# 2022_AESK_UAV_EXT_CONN.net
KiCad netlist of a schematic drawn in Altium Designer
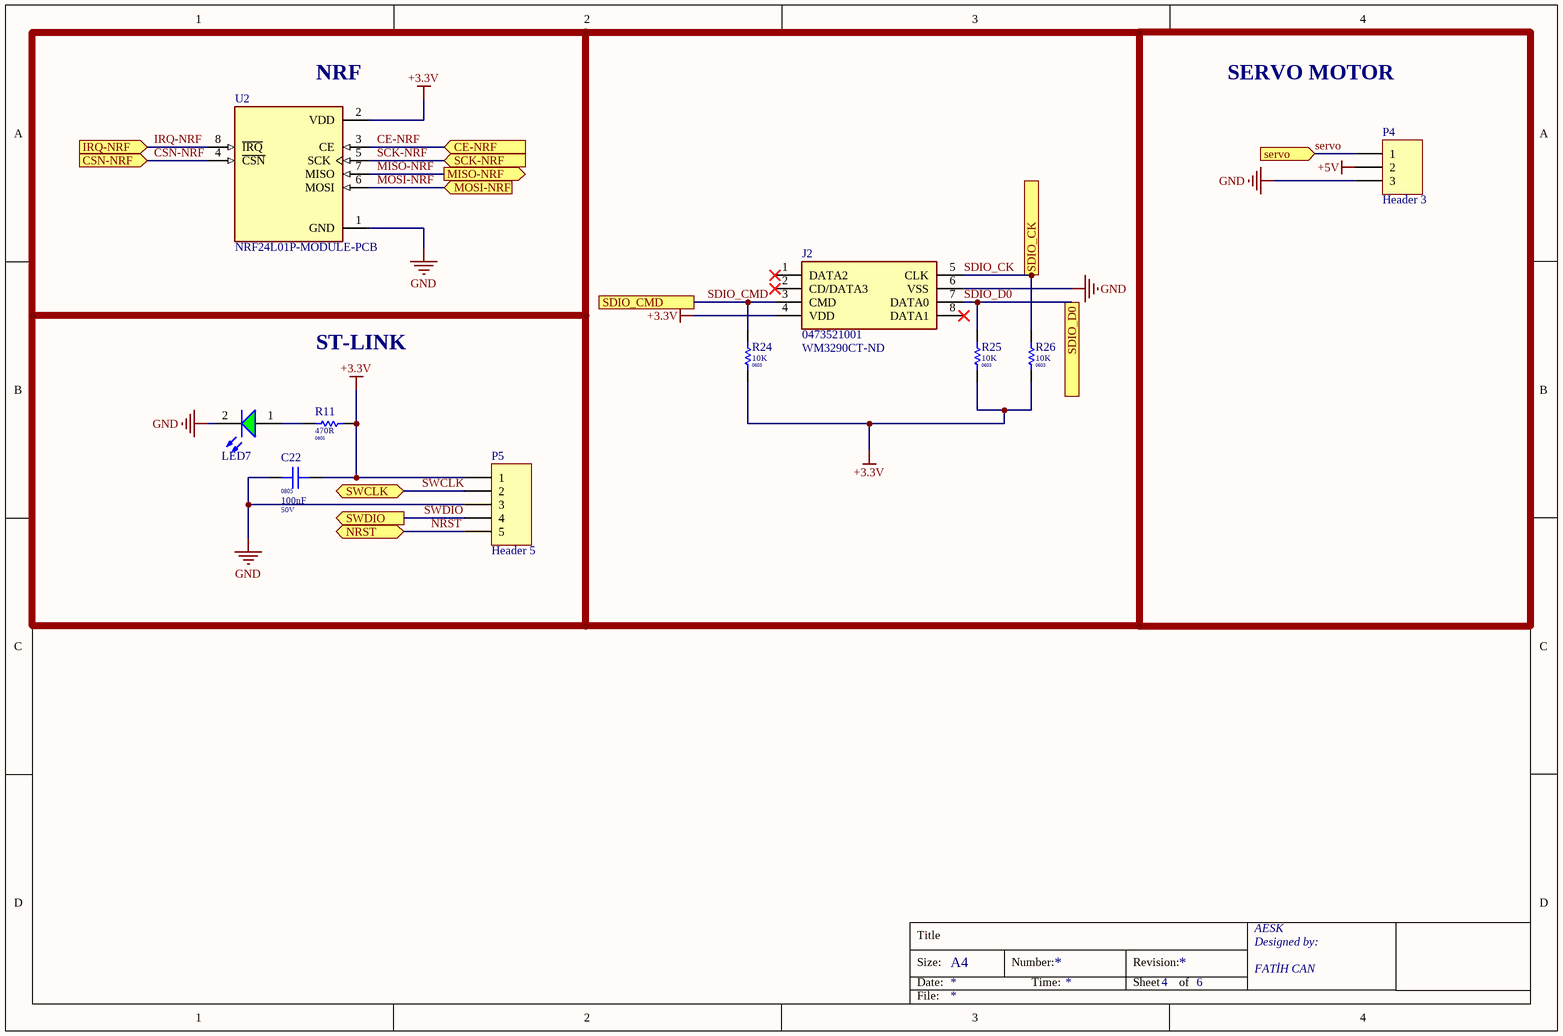
[diagram p0: 2022_AESK_UAV_EXT_CONN.SchDoc]

(export (version "E")
  (design (tool "Eeschema 10.0.6"))
  (components
    (comp (ref "C22")
      (value "100nF")
      (footprint "CAPC 0805")
      (description "Capacitor Ceramic 100nF 50V 0805")
      (fields
        (field (name "TOLERANCE") "%10")
        (field (name "PACKAGE / CASE") "0805")
        (field (name "VOLTAGE") "50V")
        (field (name "PART NUMBER") "CAPC0572")
      )
      (libsource (lib "AESK Database Library") (part "NPCapacitor"))
    )
    (comp (ref "J2")
      (value "0473521001")
      (footprint "47352-1001")
      (description "microSD Card Module")
      (fields (field (name "SUPPLIER PART NUMBER 1") "WM3290CT-ND"))
      (libsource (lib "2022_AESK_UAV") (part "0473521001"))
    )
    (comp (ref "LED7")
      (value "~")
      (footprint "LED GREEN 0805")
      (description "LED")
      (libsource (lib "Diodes_GESK") (part "LED GREEN"))
    )
    (comp (ref "P4")
      (value "Header 3")
      (footprint "HDR1X3")
      (description "Header, 3-Pin")
      (fields (field (name "PUBLISHER") "Altium Limited"))
      (libsource (lib "Miscellaneous Connectors") (part "Header 3"))
    )
    (comp (ref "P5")
      (value "Header 5")
      (footprint "HDR1X5")
      (description "Header, 5-Pin")
      (fields (field (name "PUBLISHER") "Altium Limited"))
      (libsource (lib "Miscellaneous Connectors") (part "Header 5"))
    )
    (comp (ref "R11")
      (value "470R")
      (footprint "RESC 0805")
      (description "470R 0805")
      (fields
        (field (name "TOLERANCE") "%5")
        (field (name "POWER") "1/10W")
        (field (name "PACKAGE / CASE") "0805")
      )
      (libsource (lib "AESK Database Library") (part "Resistor"))
    )
    (comp (ref "R24")
      (value "10K")
      (footprint "RESC 0603")
      (description "10K 0603")
      (fields
        (field (name "TOLERANCE") "%5")
        (field (name "POWER") "1/10W")
        (field (name "PACKAGE / CASE") "0603")
      )
      (libsource (lib "AESK Database Library") (part "Resistor"))
    )
    (comp (ref "R25")
      (value "10K")
      (footprint "RESC 0603")
      (description "10K 0603")
      (fields
        (field (name "TOLERANCE") "%5")
        (field (name "POWER") "1/10W")
        (field (name "PACKAGE / CASE") "0603")
      )
      (libsource (lib "AESK Database Library") (part "Resistor"))
    )
    (comp (ref "R26")
      (value "10K")
      (footprint "RESC 0603")
      (description "10K 0603")
      (fields
        (field (name "TOLERANCE") "%5")
        (field (name "POWER") "1/10W")
        (field (name "PACKAGE / CASE") "0603")
      )
      (libsource (lib "AESK Database Library") (part "Resistor"))
    )
    (comp (ref "U2")
      (value "NRF24L01P-MODULE-PCB")
      (footprint "nrf")
      (description "- Transceiver For Use With nRF24L01+")
      (fields (field (name "MF") "Nordic Semiconductor"))
      (libsource (lib "UAV_UcusKontrolKartı_Sematik_Kutuphane") (part "NRF24L01P-MODULE-PCB"))
    )
  )
  (nets
    (net (code "1") (name "+3.3V") (class "Default")
      (node (ref "C22") (pin "2") (pinfunction "2_2") (pintype "passive"))
      (node (ref "J2") (pin "4") (pinfunction "VDD_4") (pintype "passive"))
      (node (ref "P5") (pin "1") (pinfunction "1_1") (pintype "passive"))
      (node (ref "R11") (pin "2") (pinfunction "2_2") (pintype "passive"))
      (node (ref "R24") (pin "1") (pinfunction "1_1") (pintype "passive"))
      (node (ref "R25") (pin "1") (pinfunction "1_1") (pintype "passive"))
      (node (ref "R26") (pin "1") (pinfunction "1_1") (pintype "passive"))
      (node (ref "U2") (pin "2") (pinfunction "VDD_2") (pintype "power_in"))
    )
    (net (code "2") (name "+5V") (class "Default")
      (node (ref "P4") (pin "2") (pinfunction "2_2") (pintype "passive"))
    )
    (net (code "3") (name "/CE-NRF") (class "Default")
      (node (ref "U2") (pin "3") (pinfunction "CE_3") (pintype "input"))
    )
    (net (code "4") (name "/CSN-NRF") (class "Default")
      (node (ref "U2") (pin "4") (pinfunction "~{CSN}_4") (pintype "input"))
    )
    (net (code "5") (name "/IRQ-NRF") (class "Default")
      (node (ref "U2") (pin "8") (pinfunction "~{IRQ}_8") (pintype "input"))
    )
    (net (code "6") (name "/MISO-NRF") (class "Default")
      (node (ref "U2") (pin "7") (pinfunction "MISO_7") (pintype "input"))
    )
    (net (code "7") (name "/MOSI-NRF") (class "Default")
      (node (ref "U2") (pin "6") (pinfunction "MOSI_6") (pintype "input"))
    )
    (net (code "8") (name "/NRST") (class "Default")
      (node (ref "P5") (pin "5") (pinfunction "5_5") (pintype "passive"))
    )
    (net (code "9") (name "/SCK-NRF") (class "Default")
      (node (ref "U2") (pin "5") (pinfunction "SCK_5") (pintype "input"))
    )
    (net (code "10") (name "/SDIO_CK") (class "Default")
      (node (ref "J2") (pin "5") (pinfunction "CLK_5") (pintype "passive"))
      (node (ref "R26") (pin "2") (pinfunction "2_2") (pintype "passive"))
    )
    (net (code "11") (name "/SDIO_CMD") (class "Default")
      (node (ref "J2") (pin "3") (pinfunction "CMD_3") (pintype "passive"))
      (node (ref "R24") (pin "2") (pinfunction "2_2") (pintype "passive"))
    )
    (net (code "12") (name "/SDIO_D0") (class "Default")
      (node (ref "J2") (pin "7") (pinfunction "DATA0_7") (pintype "passive"))
      (node (ref "R25") (pin "2") (pinfunction "2_2") (pintype "passive"))
    )
    (net (code "13") (name "/SWCLK") (class "Default")
      (node (ref "P5") (pin "2") (pinfunction "2_2") (pintype "passive"))
    )
    (net (code "14") (name "/SWDIO") (class "Default")
      (node (ref "P5") (pin "4") (pinfunction "4_4") (pintype "passive"))
    )
    (net (code "15") (name "/servo") (class "Default")
      (node (ref "P4") (pin "1") (pinfunction "1_1") (pintype "passive"))
    )
    (net (code "16") (name "GND") (class "Default")
      (node (ref "C22") (pin "1") (pinfunction "1_1") (pintype "passive"))
      (node (ref "J2") (pin "6") (pinfunction "VSS_6") (pintype "passive"))
      (node (ref "LED7") (pin "2") (pinfunction "C_2") (pintype "passive"))
      (node (ref "P4") (pin "3") (pinfunction "3_3") (pintype "passive"))
      (node (ref "P5") (pin "3") (pinfunction "3_3") (pintype "passive"))
      (node (ref "U2") (pin "1") (pinfunction "GND_1") (pintype "power_in"))
    )
    (net (code "17") (name "Net-(LED7-A)") (class "Default")
      (node (ref "LED7") (pin "1") (pinfunction "A_1") (pintype "passive"))
      (node (ref "R11") (pin "1") (pinfunction "1_1") (pintype "passive"))
    )
    (net (code "18") (name "unconnected-(J2-CD{slash}DATA3-Pad2)") (class "Default")
      (node (ref "J2") (pin "2") (pinfunction "CD/DATA3_2") (pintype "passive+no_connect"))
    )
    (net (code "19") (name "unconnected-(J2-DATA1-Pad8)") (class "Default")
      (node (ref "J2") (pin "8") (pinfunction "DATA1_8") (pintype "passive+no_connect"))
    )
    (net (code "20") (name "unconnected-(J2-DATA2-Pad1)") (class "Default")
      (node (ref "J2") (pin "1") (pinfunction "DATA2_1") (pintype "passive+no_connect"))
    )
  )
)
